# Schematic_Open433_2020-06-17_01-57-08.net
KiCad netlist of a schematic drawn in EasyEDA
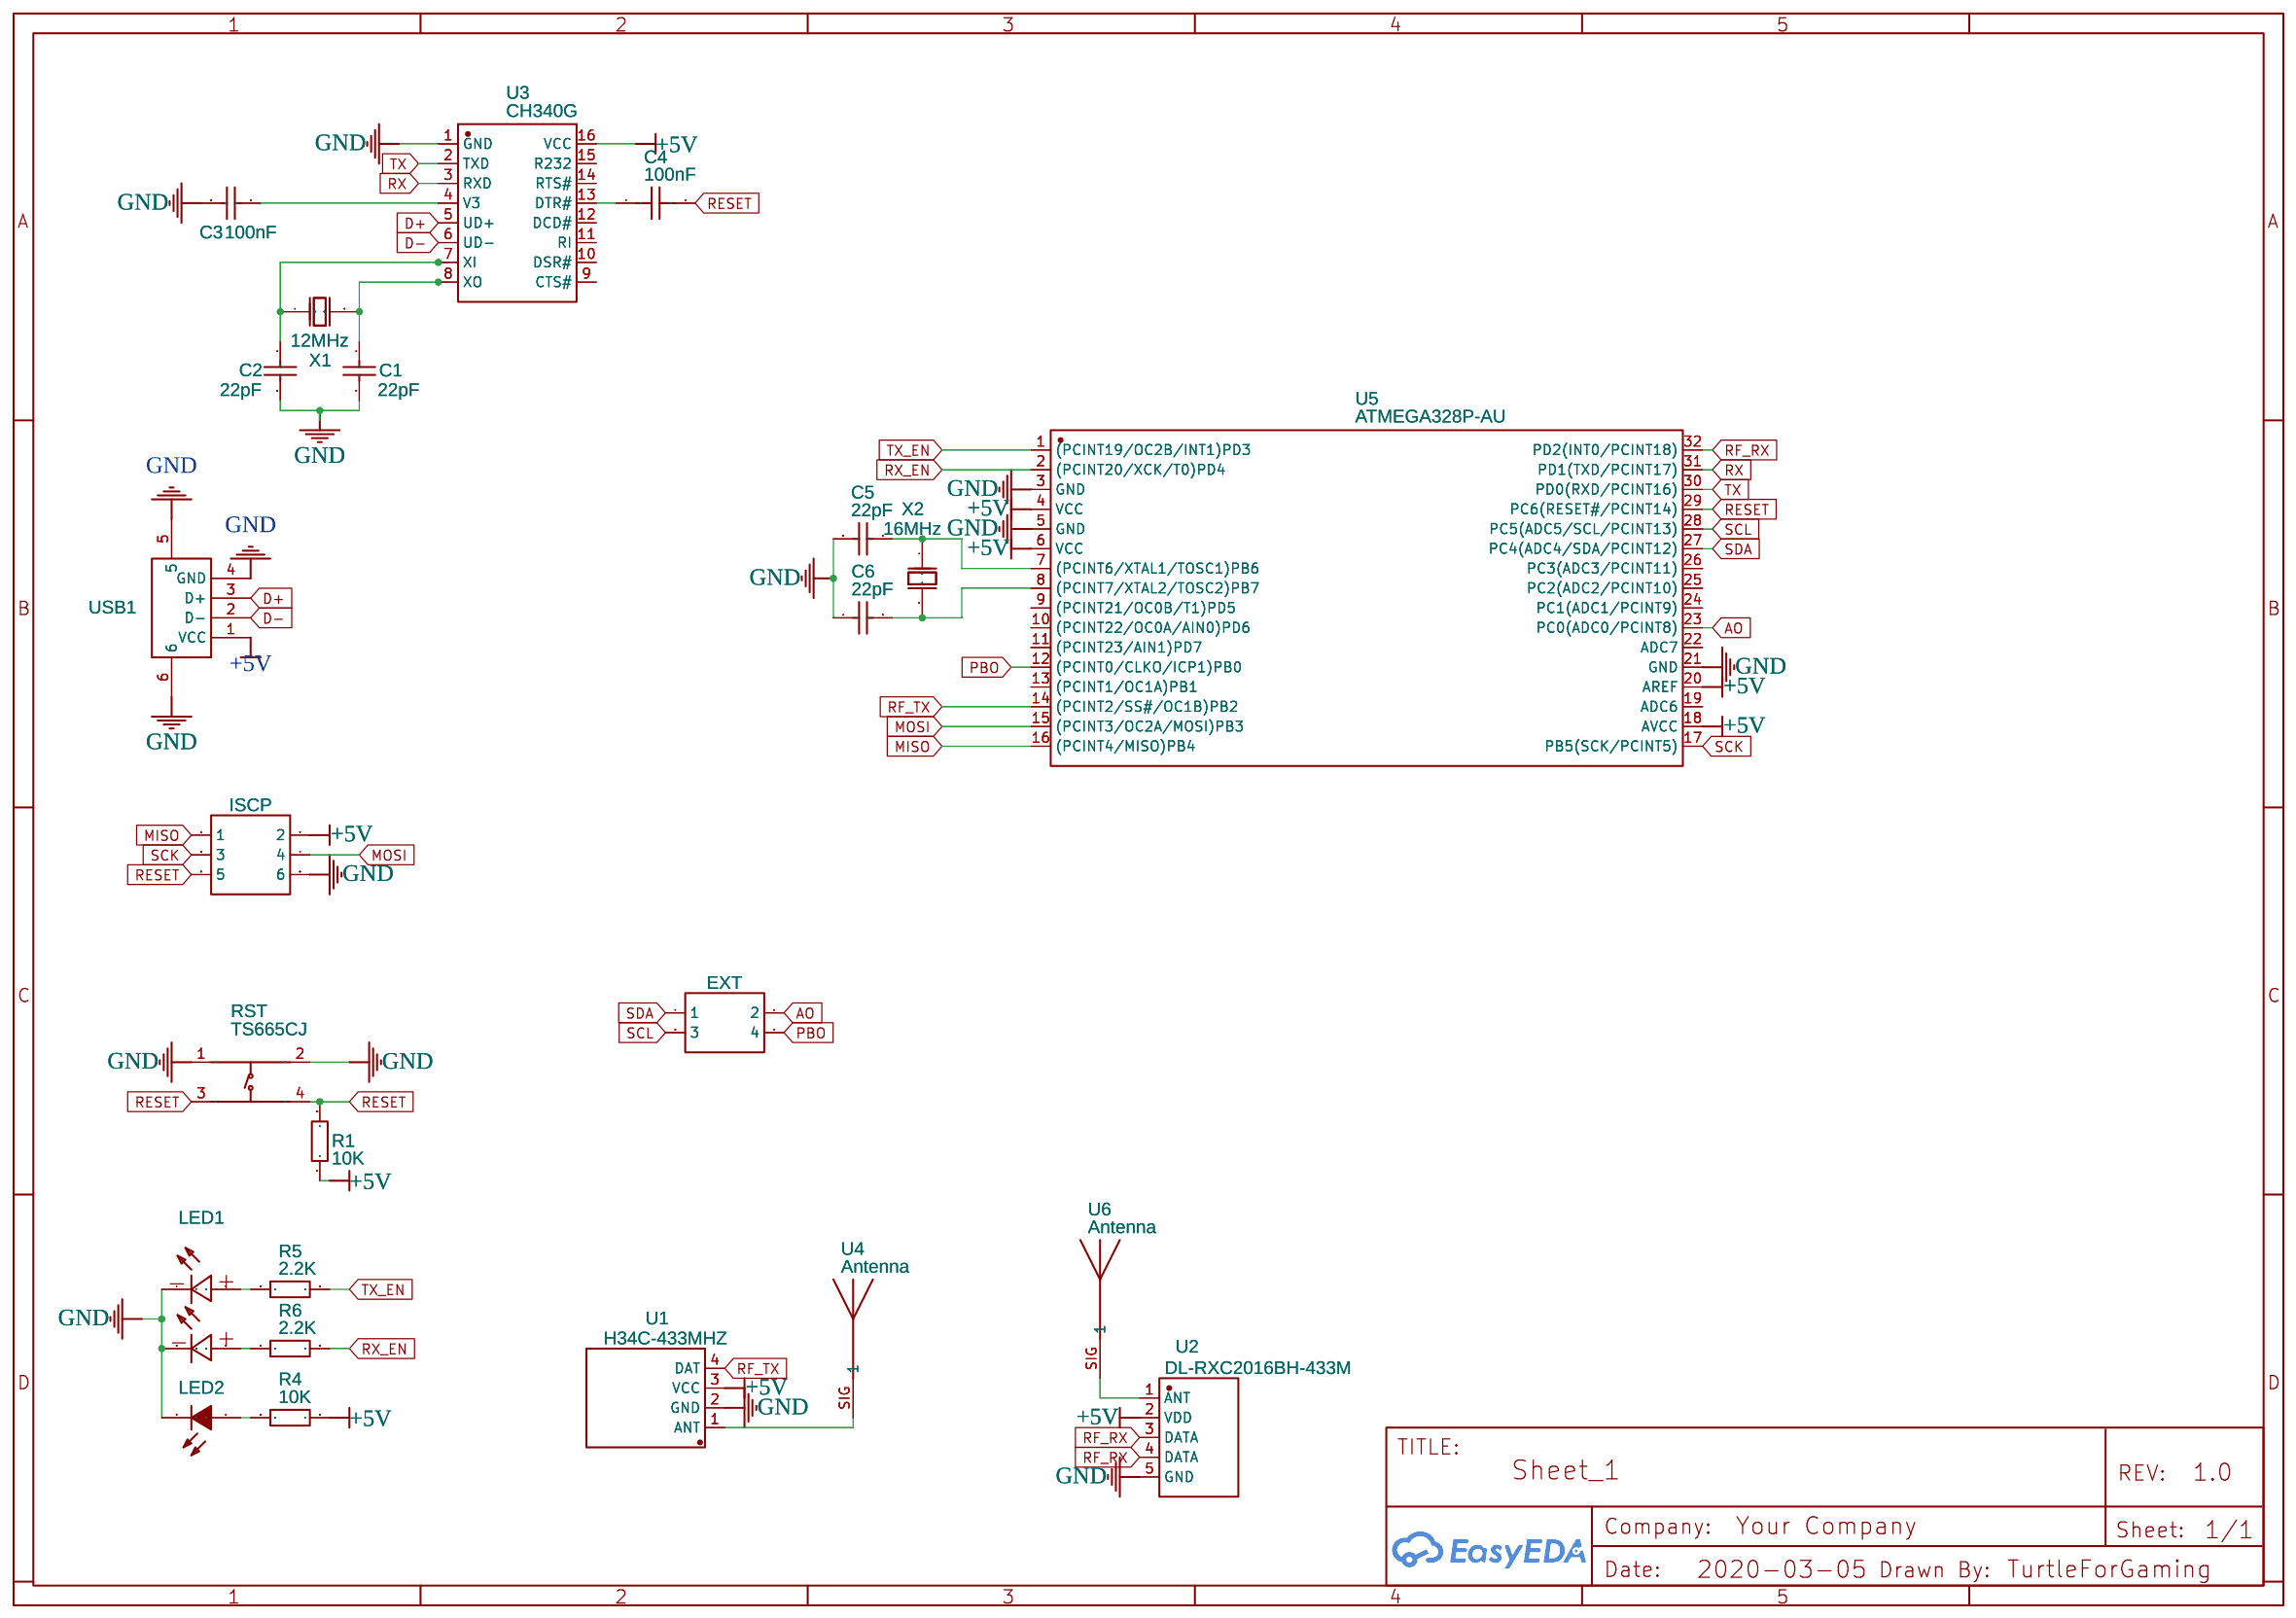
[diagram p0: schematic sheet]

(export (version "E")
  (design (tool "Eeschema 10.0.6"))
  (components
    (comp (ref "C1")
      (value "22pF")
      (fields
        (field (name "BOM_Manufacturer Part") "1206CG220J500NT")
        (field (name "BOM_Supplier Part") "C1896")
      )
      (libsource (lib "") (part "1206CG220J500NT_2"))
    )
    (comp (ref "C2")
      (value "22pF")
      (fields
        (field (name "BOM_Manufacturer Part") "1206CG220J500NT")
        (field (name "BOM_Supplier Part") "C1896")
      )
      (libsource (lib "") (part "1206CG220J500NT_2"))
    )
    (comp (ref "C3")
      (value "100nF")
      (fields
        (field (name "BOM_Manufacturer Part") "GRM31C5C1H104JA01L")
        (field (name "BOM_Supplier Part") "C97946")
      )
      (libsource (lib "") (part "GRM31C5C1H104JA01L"))
    )
    (comp (ref "C4")
      (value "100nF")
      (fields
        (field (name "BOM_Manufacturer Part") "FM31X104K251EEG")
        (field (name "BOM_Supplier Part") "C365814")
      )
      (libsource (lib "") (part "FM31X104K251EEG"))
    )
    (comp (ref "C5")
      (value "22pF")
      (fields
        (field (name "BOM_Manufacturer Part") "1206CG220J500NT")
        (field (name "BOM_Supplier Part") "C1896")
      )
      (libsource (lib "") (part "1206CG220J500NT"))
    )
    (comp (ref "C6")
      (value "22pF")
      (fields
        (field (name "BOM_Manufacturer Part") "1206CG220J500NT")
        (field (name "BOM_Supplier Part") "C1896")
      )
      (libsource (lib "") (part "1206CG220J500NT_1"))
    )
    (comp (ref "EXT")
      (value "HDR-M-2.54_2x2")
      (fields (field (name "BOM_Supplier Part") "C66690"))
      (libsource (lib "") (part "HDR-M-2.54_2x2"))
    )
    (comp (ref "ISCP")
      (value "Header-Female-2.54_2x3")
      (fields
        (field (name "BOM_Manufacturer Part") "DS1023-2*3SF11")
        (field (name "BOM_Supplier Part") "C92272")
      )
      (libsource (lib "") (part "Header-Female-2.54_2x3"))
    )
    (comp (ref "LED1")
      (value "19-223/Y2R6C-A01/2T")
      (fields (field (name "BOM_Supplier Part") "C282134"))
      (libsource (lib "") (part "19-223/Y2R6C-A01/2T"))
    )
    (comp (ref "LED2")
      (value "19-217/GHC-YR1S2/3T")
      (fields (field (name "BOM_Supplier Part") "C72043"))
      (libsource (lib "") (part "19-217/GHC-YR1S2/3T"))
    )
    (comp (ref "R1")
      (value "10K")
      (fields
        (field (name "BOM_Manufacturer Part") "CR-06JL7---10K")
        (field (name "BOM_Supplier Part") "C280032")
      )
      (libsource (lib "") (part "CR-06JL7---10K_1"))
    )
    (comp (ref "R4")
      (value "10K")
      (fields
        (field (name "BOM_Manufacturer Part") "CR-06JL7---10K")
        (field (name "BOM_Supplier Part") "C280032")
      )
      (libsource (lib "") (part "CR-06JL7---10K"))
    )
    (comp (ref "R5")
      (value "2.2K")
      (fields
        (field (name "BOM_Manufacturer Part") "QR0603F2K2P05")
        (field (name "BOM_Supplier Part") "C176136")
      )
      (libsource (lib "") (part "QR0603F2K2P05"))
    )
    (comp (ref "R6")
      (value "2.2K")
      (fields
        (field (name "BOM_Manufacturer Part") "QR0603F2K2P05")
        (field (name "BOM_Supplier Part") "C176136")
      )
      (libsource (lib "") (part "QR0603F2K2P05"))
    )
    (comp (ref "RST")
      (value "TS665CJ")
      (fields (field (name "BOM_Supplier Part") "C393938"))
      (libsource (lib "") (part "TS665CJ"))
    )
    (comp (ref "U1")
      (value "H34C-433MHZ")
      (fields (field (name "BOM_Supplier Part") "C131030"))
      (libsource (lib "") (part "H34C-433MHZ"))
    )
    (comp (ref "U2")
      (value "DL-RXC2016BH-433M")
      (fields (field (name "BOM_Supplier Part") "C381154"))
      (libsource (lib "") (part "DL-RXC2016BH-433M"))
    )
    (comp (ref "U3")
      (value "CH340G")
      (fields (field (name "BOM_Supplier Part") "C14267"))
      (libsource (lib "") (part "CH340G"))
    )
    (comp (ref "U4")
      (value "Antenna")
      (fields (field (name "BOM_Manufacturer Part") "ANT"))
      (libsource (lib "") (part "Antenna"))
    )
    (comp (ref "U5")
      (value "ATMEGA328P-AU")
      (fields (field (name "BOM_Supplier Part") "C14877"))
      (libsource (lib "") (part "ATMEGA328P-AU"))
    )
    (comp (ref "U6")
      (value "Antenna")
      (fields (field (name "BOM_Manufacturer Part") "ANT"))
      (libsource (lib "") (part "Antenna"))
    )
    (comp (ref "USB1")
      (value "U217-04XN-XXR84")
      (fields (field (name "BOM_Supplier Part") "C319178"))
      (libsource (lib "") (part "U217-04XN-XXR84"))
    )
    (comp (ref "X1")
      (value "12MHz")
      (fields
        (field (name "BOM_Manufacturer Part") "C12000J517")
        (field (name "BOM_Supplier Part") "C279578")
      )
      (libsource (lib "") (part "C12000J517"))
    )
    (comp (ref "X2")
      (value "16MHz")
      (fields
        (field (name "BOM_Manufacturer Part") "49MD-16.000-20-20-20/A")
        (field (name "BOM_Supplier Part") "C240963")
      )
      (libsource (lib "") (part "49MD-16.000-20-20-20/A"))
    )
  )
  (nets
    (net (code "1") (name "+5V") (class "Default")
      (node (ref "ISCP") (pin "2") (pinfunction "2_2") (pintype "input"))
      (node (ref "R1") (pin "1") (pinfunction "1_1") (pintype "unspecified"))
      (node (ref "R4") (pin "1") (pinfunction "1_1") (pintype "unspecified"))
      (node (ref "U1") (pin "3") (pinfunction "VCC_3") (pintype "unspecified"))
      (node (ref "U2") (pin "2") (pinfunction "VDD_2") (pintype "unspecified"))
      (node (ref "U3") (pin "16") (pinfunction "VCC_16") (pintype "unspecified"))
      (node (ref "U5") (pin "18") (pinfunction "AVCC_18") (pintype "unspecified"))
      (node (ref "U5") (pin "20") (pinfunction "AREF_20") (pintype "unspecified"))
      (node (ref "U5") (pin "4") (pinfunction "VCC_4") (pintype "unspecified"))
      (node (ref "U5") (pin "6") (pinfunction "VCC_6") (pintype "unspecified"))
      (node (ref "USB1") (pin "1") (pinfunction "VCC_1") (pintype "unspecified"))
    )
    (net (code "2") (name "AO") (class "Default")
      (node (ref "EXT") (pin "2") (pinfunction "2_2") (pintype "input"))
      (node (ref "U5") (pin "23") (pinfunction "PC0(ADC0/PCINT8)_23") (pintype "unspecified"))
    )
    (net (code "3") (name "D+") (class "Default")
      (node (ref "U3") (pin "5") (pinfunction "UD+_5") (pintype "unspecified"))
      (node (ref "USB1") (pin "3") (pinfunction "D+_3") (pintype "unspecified"))
    )
    (net (code "4") (name "D-") (class "Default")
      (node (ref "U3") (pin "6") (pinfunction "UD-_6") (pintype "unspecified"))
      (node (ref "USB1") (pin "2") (pinfunction "D-_2") (pintype "unspecified"))
    )
    (net (code "5") (name "GND") (class "Default")
      (node (ref "C1") (pin "2") (pinfunction "2_2") (pintype "input"))
      (node (ref "C2") (pin "2") (pinfunction "2_2") (pintype "input"))
      (node (ref "C3") (pin "1") (pinfunction "1_1") (pintype "input"))
      (node (ref "C5") (pin "2") (pinfunction "2_2") (pintype "input"))
      (node (ref "C6") (pin "1") (pinfunction "1_1") (pintype "input"))
      (node (ref "ISCP") (pin "6") (pinfunction "6_6") (pintype "input"))
      (node (ref "LED1") (pin "3") (pinfunction "3_3") (pintype "unspecified"))
      (node (ref "LED1") (pin "4") (pinfunction "4_4") (pintype "unspecified"))
      (node (ref "LED2") (pin "2") (pinfunction "C_2") (pintype "input"))
      (node (ref "RST") (pin "1") (pinfunction "A_1") (pintype "unspecified"))
      (node (ref "RST") (pin "2") (pinfunction "B_2") (pintype "unspecified"))
      (node (ref "U1") (pin "2") (pinfunction "GND_2") (pintype "unspecified"))
      (node (ref "U2") (pin "5") (pinfunction "GND_5") (pintype "unspecified"))
      (node (ref "U3") (pin "1") (pinfunction "GND_1") (pintype "unspecified"))
      (node (ref "U5") (pin "21") (pinfunction "GND_21") (pintype "unspecified"))
      (node (ref "U5") (pin "3") (pinfunction "GND_3") (pintype "unspecified"))
      (node (ref "U5") (pin "5") (pinfunction "GND_5") (pintype "unspecified"))
      (node (ref "USB1") (pin "4") (pinfunction "GND_4") (pintype "unspecified"))
      (node (ref "USB1") (pin "5") (pinfunction "5_5") (pintype "unspecified"))
      (node (ref "USB1") (pin "6") (pinfunction "6_6") (pintype "unspecified"))
    )
    (net (code "6") (name "MISO") (class "Default")
      (node (ref "ISCP") (pin "1") (pinfunction "1_1") (pintype "input"))
      (node (ref "U5") (pin "16") (pinfunction "(PCINT4/MISO)PB4_16") (pintype "unspecified"))
    )
    (net (code "7") (name "MOSI") (class "Default")
      (node (ref "ISCP") (pin "4") (pinfunction "4_4") (pintype "input"))
      (node (ref "U5") (pin "15") (pinfunction "(PCINT3/OC2A/MOSI)PB3_15") (pintype "unspecified"))
    )
    (net (code "8") (name "Net-(LED1-Pad1)") (class "Default")
      (node (ref "LED1") (pin "1") (pinfunction "1_1") (pintype "unspecified"))
      (node (ref "R5") (pin "1") (pinfunction "1_1") (pintype "unspecified"))
    )
    (net (code "9") (name "Net-(LED1-Pad2)") (class "Default")
      (node (ref "LED1") (pin "2") (pinfunction "2_2") (pintype "unspecified"))
      (node (ref "R6") (pin "1") (pinfunction "1_1") (pintype "unspecified"))
    )
    (net (code "10") (name "Net-(LED2-A)") (class "Default")
      (node (ref "LED2") (pin "1") (pinfunction "A_1") (pintype "input"))
      (node (ref "R4") (pin "2") (pinfunction "2_2") (pintype "unspecified"))
    )
    (net (code "11") (name "Net-(U1-ANT)") (class "Default")
      (node (ref "U1") (pin "1") (pinfunction "ANT_1") (pintype "unspecified"))
      (node (ref "U4") (pin "SIG") (pinfunction "1_SIG") (pintype "unspecified"))
    )
    (net (code "12") (name "Net-(U2-ANT)") (class "Default")
      (node (ref "U2") (pin "1") (pinfunction "ANT_1") (pintype "unspecified"))
      (node (ref "U6") (pin "SIG") (pinfunction "1_SIG") (pintype "unspecified"))
    )
    (net (code "13") (name "Net-(U3-DTR#)") (class "Default")
      (node (ref "C4") (pin "1") (pinfunction "1_1") (pintype "unspecified"))
      (node (ref "U3") (pin "13") (pinfunction "DTR#_13") (pintype "unspecified"))
    )
    (net (code "14") (name "Net-(U3-V3)") (class "Default")
      (node (ref "C3") (pin "2") (pinfunction "2_2") (pintype "input"))
      (node (ref "U3") (pin "4") (pinfunction "V3_4") (pintype "unspecified"))
    )
    (net (code "15") (name "Net-(U3-XI)") (class "Default")
      (node (ref "C2") (pin "1") (pinfunction "1_1") (pintype "input"))
      (node (ref "U3") (pin "7") (pinfunction "XI_7") (pintype "unspecified"))
      (node (ref "X1") (pin "1") (pinfunction "OSC1_1") (pintype "input"))
    )
    (net (code "16") (name "Net-(U3-XO)") (class "Default")
      (node (ref "C1") (pin "1") (pinfunction "1_1") (pintype "input"))
      (node (ref "U3") (pin "8") (pinfunction "XO_8") (pintype "unspecified"))
      (node (ref "X1") (pin "2") (pinfunction "OSC2_2") (pintype "input"))
    )
    (net (code "17") (name "Net-(U5-(PCINT6{slash}XTAL1{slash}TOSC1)PB6)") (class "Default")
      (node (ref "C5") (pin "1") (pinfunction "1_1") (pintype "input"))
      (node (ref "U5") (pin "7") (pinfunction "(PCINT6/XTAL1/TOSC1)PB6_7") (pintype "unspecified"))
      (node (ref "X2") (pin "1") (pinfunction "OSC1_1") (pintype "input"))
    )
    (net (code "18") (name "Net-(U5-(PCINT7{slash}XTAL2{slash}TOSC2)PB7)") (class "Default")
      (node (ref "C6") (pin "2") (pinfunction "2_2") (pintype "input"))
      (node (ref "U5") (pin "8") (pinfunction "(PCINT7/XTAL2/TOSC2)PB7_8") (pintype "unspecified"))
      (node (ref "X2") (pin "2") (pinfunction "OSC2_2") (pintype "input"))
    )
    (net (code "19") (name "PBO") (class "Default")
      (node (ref "EXT") (pin "4") (pinfunction "4_4") (pintype "input"))
      (node (ref "U5") (pin "12") (pinfunction "(PCINT0/CLKO/ICP1)PB0_12") (pintype "unspecified"))
    )
    (net (code "20") (name "RESET") (class "Default")
      (node (ref "C4") (pin "2") (pinfunction "2_2") (pintype "unspecified"))
      (node (ref "ISCP") (pin "5") (pinfunction "5_5") (pintype "input"))
      (node (ref "R1") (pin "2") (pinfunction "2_2") (pintype "unspecified"))
      (node (ref "RST") (pin "3") (pinfunction "C_3") (pintype "unspecified"))
      (node (ref "RST") (pin "4") (pinfunction "D_4") (pintype "unspecified"))
      (node (ref "U5") (pin "29") (pinfunction "PC6(RESET#/PCINT14)_29") (pintype "unspecified"))
    )
    (net (code "21") (name "RF_RX") (class "Default")
      (node (ref "U2") (pin "3") (pinfunction "DATA_3") (pintype "unspecified"))
      (node (ref "U2") (pin "4") (pinfunction "DATA_4") (pintype "unspecified"))
      (node (ref "U5") (pin "32") (pinfunction "PD2(INT0/PCINT18)_32") (pintype "unspecified"))
    )
    (net (code "22") (name "RF_TX") (class "Default")
      (node (ref "U1") (pin "4") (pinfunction "DAT_4") (pintype "unspecified"))
      (node (ref "U5") (pin "14") (pinfunction "(PCINT2/SS#/OC1B)PB2_14") (pintype "unspecified"))
    )
    (net (code "23") (name "RX") (class "Default")
      (node (ref "U3") (pin "3") (pinfunction "RXD_3") (pintype "unspecified"))
      (node (ref "U5") (pin "31") (pinfunction "PD1(TXD/PCINT17)_31") (pintype "unspecified"))
    )
    (net (code "24") (name "RX_EN") (class "Default")
      (node (ref "R6") (pin "2") (pinfunction "2_2") (pintype "unspecified"))
      (node (ref "U5") (pin "2") (pinfunction "(PCINT20/XCK/T0)PD4_2") (pintype "unspecified"))
    )
    (net (code "25") (name "SCK") (class "Default")
      (node (ref "ISCP") (pin "3") (pinfunction "3_3") (pintype "input"))
      (node (ref "U5") (pin "17") (pinfunction "PB5(SCK/PCINT5)_17") (pintype "unspecified"))
    )
    (net (code "26") (name "SCL") (class "Default")
      (node (ref "EXT") (pin "3") (pinfunction "3_3") (pintype "input"))
      (node (ref "U5") (pin "28") (pinfunction "PC5(ADC5/SCL/PCINT13)_28") (pintype "unspecified"))
    )
    (net (code "27") (name "SDA") (class "Default")
      (node (ref "EXT") (pin "1") (pinfunction "1_1") (pintype "input"))
      (node (ref "U5") (pin "27") (pinfunction "PC4(ADC4/SDA/PCINT12)_27") (pintype "unspecified"))
    )
    (net (code "28") (name "TX") (class "Default")
      (node (ref "U3") (pin "2") (pinfunction "TXD_2") (pintype "unspecified"))
      (node (ref "U5") (pin "30") (pinfunction "PD0(RXD/PCINT16)_30") (pintype "unspecified"))
    )
    (net (code "29") (name "TX_EN") (class "Default")
      (node (ref "R5") (pin "2") (pinfunction "2_2") (pintype "unspecified"))
      (node (ref "U5") (pin "1") (pinfunction "(PCINT19/OC2B/INT1)PD3_1") (pintype "unspecified"))
    )
    (net (code "30") (name "unconnected-(U3-CTS#-Pad9)") (class "Default")
      (node (ref "U3") (pin "9") (pinfunction "CTS#_9") (pintype "unspecified"))
    )
    (net (code "31") (name "unconnected-(U3-DCD#-Pad12)") (class "Default")
      (node (ref "U3") (pin "12") (pinfunction "DCD#_12") (pintype "unspecified"))
    )
    (net (code "32") (name "unconnected-(U3-DSR#-Pad10)") (class "Default")
      (node (ref "U3") (pin "10") (pinfunction "DSR#_10") (pintype "unspecified"))
    )
    (net (code "33") (name "unconnected-(U3-R232-Pad15)") (class "Default")
      (node (ref "U3") (pin "15") (pinfunction "R232_15") (pintype "unspecified"))
    )
    (net (code "34") (name "unconnected-(U3-RI-Pad11)") (class "Default")
      (node (ref "U3") (pin "11") (pinfunction "RI_11") (pintype "unspecified"))
    )
    (net (code "35") (name "unconnected-(U3-RTS#-Pad14)") (class "Default")
      (node (ref "U3") (pin "14") (pinfunction "RTS#_14") (pintype "unspecified"))
    )
    (net (code "36") (name "unconnected-(U5-(PCINT1{slash}OC1A)PB1-Pad13)") (class "Default")
      (node (ref "U5") (pin "13") (pinfunction "(PCINT1/OC1A)PB1_13") (pintype "unspecified"))
    )
    (net (code "37") (name "unconnected-(U5-(PCINT21{slash}OC0B{slash}T1)PD5-Pad9)") (class "Default")
      (node (ref "U5") (pin "9") (pinfunction "(PCINT21/OC0B/T1)PD5_9") (pintype "unspecified"))
    )
    (net (code "38") (name "unconnected-(U5-(PCINT22{slash}OC0A{slash}AIN0)PD6-Pad10)") (class "Default")
      (node (ref "U5") (pin "10") (pinfunction "(PCINT22/OC0A/AIN0)PD6_10") (pintype "unspecified"))
    )
    (net (code "39") (name "unconnected-(U5-(PCINT23{slash}AIN1)PD7-Pad11)") (class "Default")
      (node (ref "U5") (pin "11") (pinfunction "(PCINT23/AIN1)PD7_11") (pintype "unspecified"))
    )
    (net (code "40") (name "unconnected-(U5-ADC6-Pad19)") (class "Default")
      (node (ref "U5") (pin "19") (pinfunction "ADC6_19") (pintype "unspecified"))
    )
    (net (code "41") (name "unconnected-(U5-ADC7-Pad22)") (class "Default")
      (node (ref "U5") (pin "22") (pinfunction "ADC7_22") (pintype "unspecified"))
    )
    (net (code "42") (name "unconnected-(U5-PC1(ADC1{slash}PCINT9)-Pad24)") (class "Default")
      (node (ref "U5") (pin "24") (pinfunction "PC1(ADC1/PCINT9)_24") (pintype "unspecified"))
    )
    (net (code "43") (name "unconnected-(U5-PC2(ADC2{slash}PCINT10)-Pad25)") (class "Default")
      (node (ref "U5") (pin "25") (pinfunction "PC2(ADC2/PCINT10)_25") (pintype "unspecified"))
    )
    (net (code "44") (name "unconnected-(U5-PC3(ADC3{slash}PCINT11)-Pad26)") (class "Default")
      (node (ref "U5") (pin "26") (pinfunction "PC3(ADC3/PCINT11)_26") (pintype "unspecified"))
    )
  )
)
